# STM32F407.net
KiCad netlist of a schematic drawn in Altium Designer
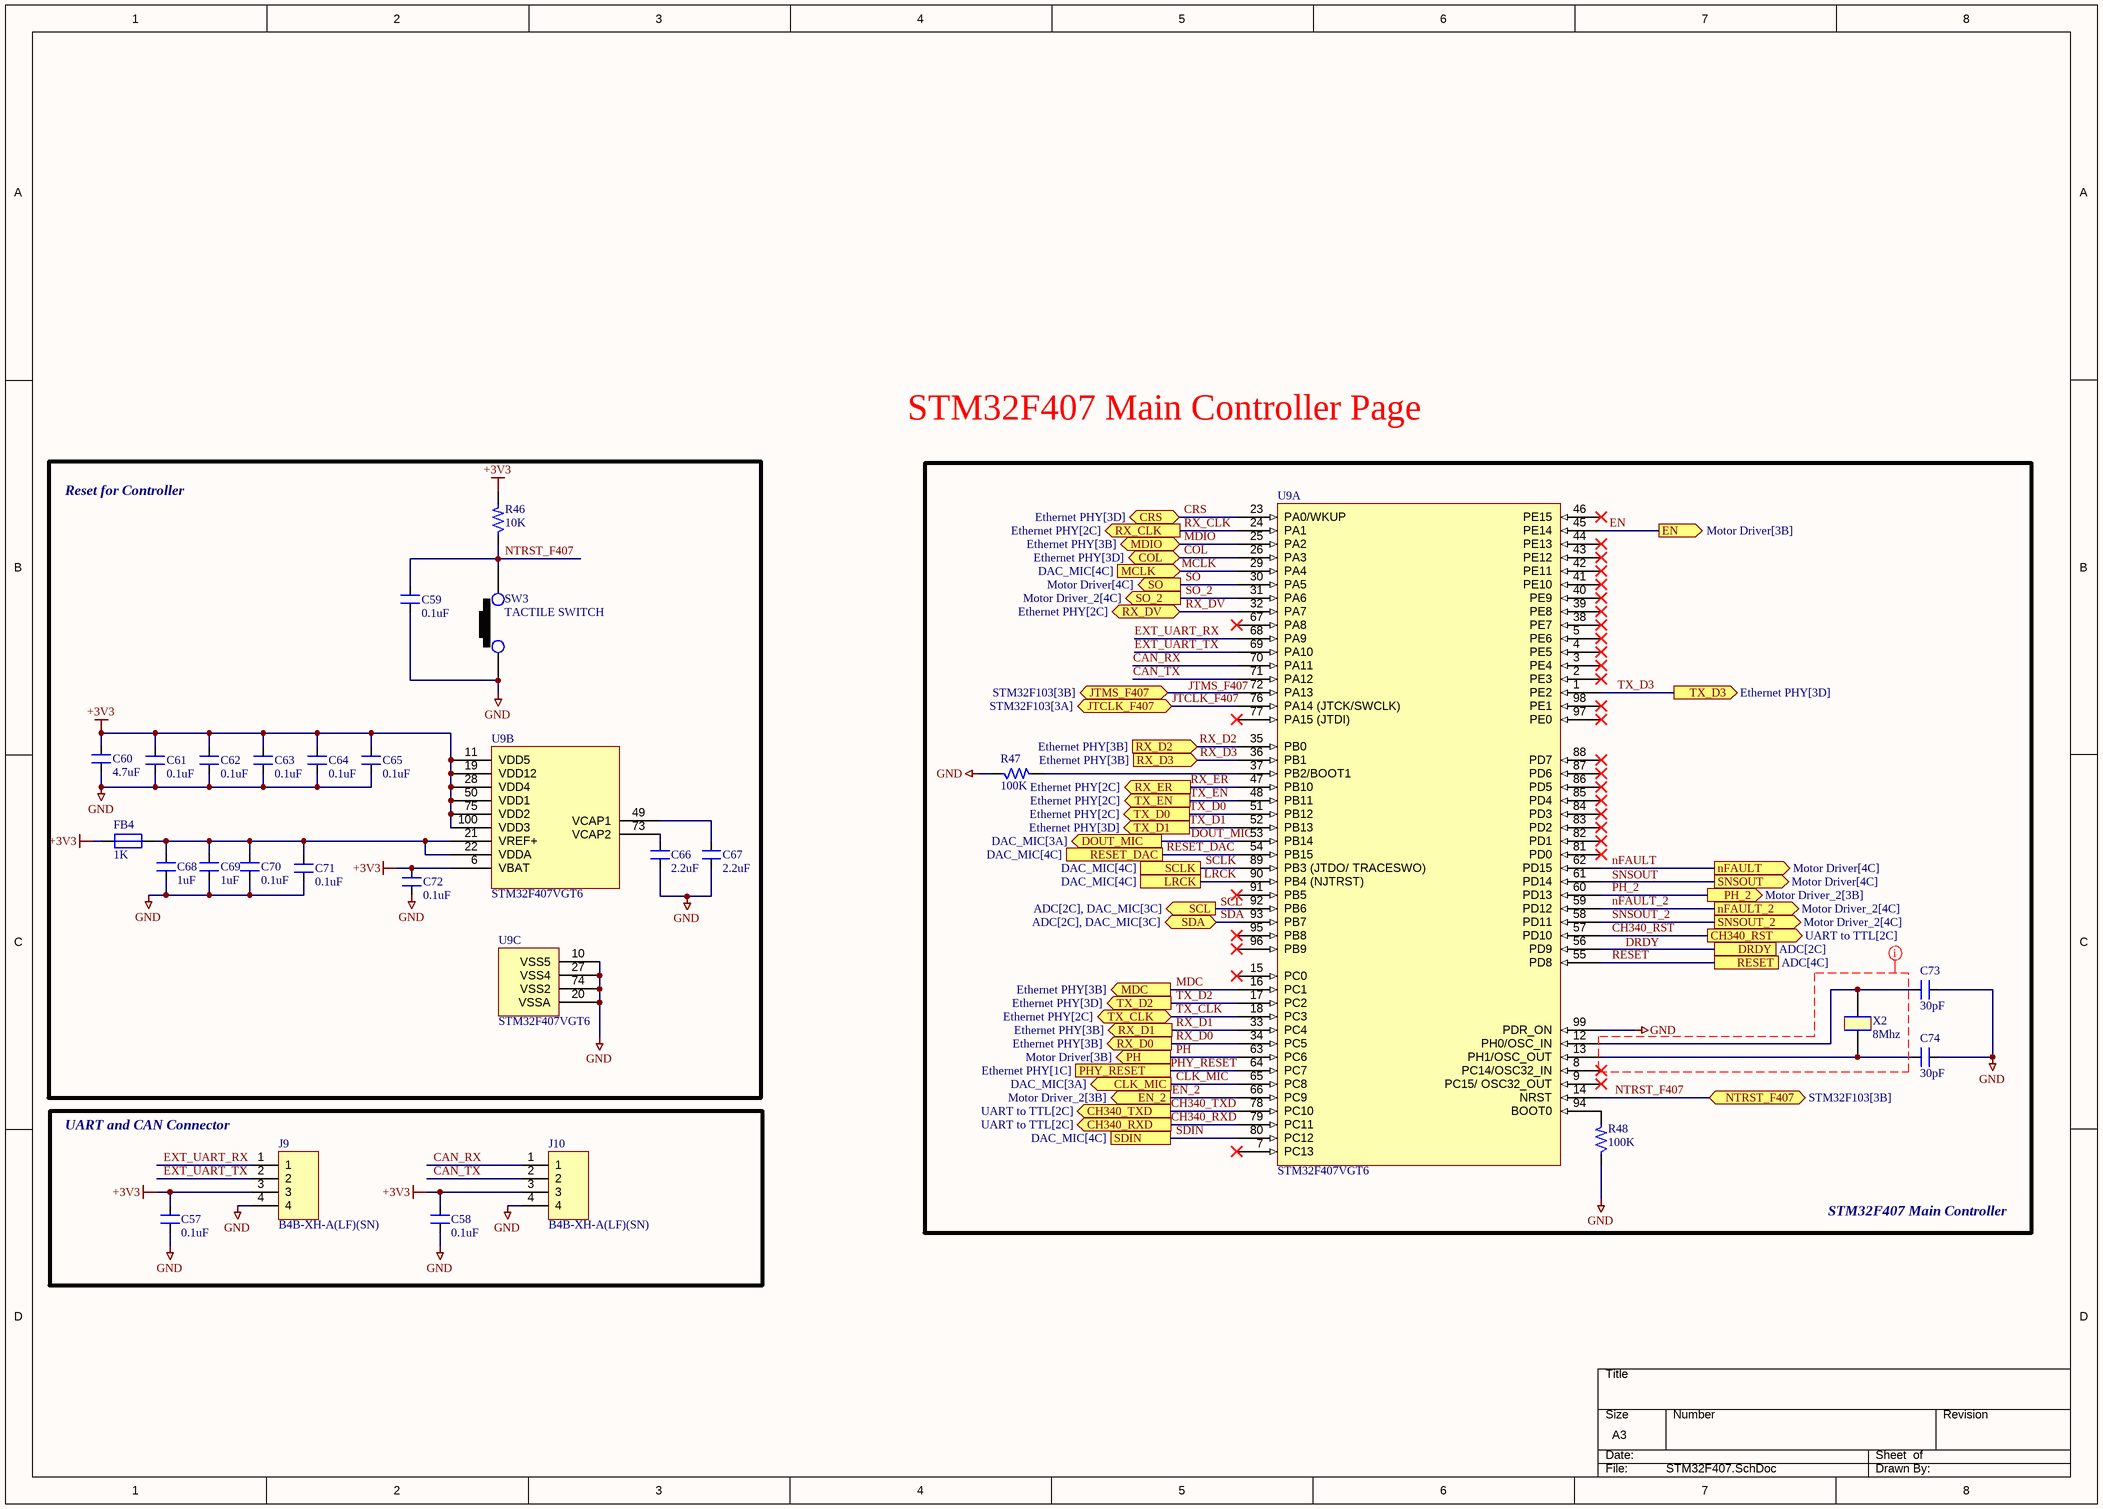
[diagram p0: STM32F407.SchDoc]

(export (version "E")
  (design (tool "Eeschema 10.0.6"))
  (components
    (comp (ref "C57")
      (value "0.1uF")
      (footprint "CAP_0805")
      (description "0.1µF ±10% 50V Ceramic Capacitor X7R 0805 (2012 Metric)")
      (fields
        (field (name "MANUFACTURER") "Samsung")
        (field (name "MANUFACTURER PART NUMBER") "CL21B104KBCNNNC")
      )
      (libsource (lib "ESTEEMPCBLIB") (part "CAP_0.1uF-50V-10%-0805"))
    )
    (comp (ref "C58")
      (value "0.1uF")
      (footprint "CAP_0805")
      (description "0.1µF ±10% 50V Ceramic Capacitor X7R 0805 (2012 Metric)")
      (fields
        (field (name "MANUFACTURER") "Samsung")
        (field (name "MANUFACTURER PART NUMBER") "CL21B104KBCNNNC")
      )
      (libsource (lib "ESTEEMPCBLIB") (part "CAP_0.1uF-50V-10%-0805"))
    )
    (comp (ref "C59")
      (value "0.1uF")
      (footprint "CAP_0805")
      (description "0.1µF ±20% 50V Ceramic Capacitor X7R 0805 (2012 Metric)")
      (fields
        (field (name "MANUFACTURER") "Samsung Electro-Mechanics")
        (field (name "MANUFACTURER PART NUMBER") "CL21B104MBCNNNC")
      )
      (libsource (lib "ESTEEMPCBLIB") (part "CAP_0.1uF-50V-20%-0805"))
    )
    (comp (ref "C60")
      (value "4.7uF")
      (footprint "CAP_0805")
      (description "4.7µF ±10% 50V Ceramic Capacitor X5R 0805 (2012 Metric)")
      (fields
        (field (name "MANUFACTURER") "Yageo")
        (field (name "MANUFACTURER PART NUMBER") "GRM21BR61H475KE51L")
      )
      (libsource (lib "ESTEEMPCBLIB") (part "CAP_4.7uF-50V-10%-0805"))
    )
    (comp (ref "C61")
      (value "0.1uF")
      (footprint "CAP_0805")
      (description "0.1µF ±20% 50V Ceramic Capacitor X7R 0805 (2012 Metric)")
      (fields
        (field (name "MANUFACTURER") "Samsung Electro-Mechanics")
        (field (name "MANUFACTURER PART NUMBER") "CL21B104MBCNNNC")
      )
      (libsource (lib "ESTEEMPCBLIB") (part "CAP_0.1uF-50V-20%-0805"))
    )
    (comp (ref "C62")
      (value "0.1uF")
      (footprint "CAP_0805")
      (description "0.1µF ±20% 50V Ceramic Capacitor X7R 0805 (2012 Metric)")
      (fields
        (field (name "MANUFACTURER") "Samsung Electro-Mechanics")
        (field (name "MANUFACTURER PART NUMBER") "CL21B104MBCNNNC")
      )
      (libsource (lib "ESTEEMPCBLIB") (part "CAP_0.1uF-50V-20%-0805"))
    )
    (comp (ref "C63")
      (value "0.1uF")
      (footprint "CAP_0805")
      (description "0.1µF ±20% 50V Ceramic Capacitor X7R 0805 (2012 Metric)")
      (fields
        (field (name "MANUFACTURER") "Samsung Electro-Mechanics")
        (field (name "MANUFACTURER PART NUMBER") "CL21B104MBCNNNC")
      )
      (libsource (lib "ESTEEMPCBLIB") (part "CAP_0.1uF-50V-20%-0805"))
    )
    (comp (ref "C64")
      (value "0.1uF")
      (footprint "CAP_0805")
      (description "0.1µF ±20% 50V Ceramic Capacitor X7R 0805 (2012 Metric)")
      (fields
        (field (name "MANUFACTURER") "Samsung Electro-Mechanics")
        (field (name "MANUFACTURER PART NUMBER") "CL21B104MBCNNNC")
      )
      (libsource (lib "ESTEEMPCBLIB") (part "CAP_0.1uF-50V-20%-0805"))
    )
    (comp (ref "C65")
      (value "0.1uF")
      (footprint "CAP_0805")
      (description "0.1µF ±20% 50V Ceramic Capacitor X7R 0805 (2012 Metric)")
      (fields
        (field (name "MANUFACTURER") "Samsung Electro-Mechanics")
        (field (name "MANUFACTURER PART NUMBER") "CL21B104MBCNNNC")
      )
      (libsource (lib "ESTEEMPCBLIB") (part "CAP_0.1uF-50V-20%-0805"))
    )
    (comp (ref "C66")
      (value "2.2uF")
      (footprint "CAP_0805")
      (description "2.2µF ±10% 25V Ceramic Capacitor X7R 0805 (2012 Metric)")
      (fields
        (field (name "MANUFACTURER") "KEMET")
        (field (name "MANUFACTURER PART NUMBER") "CL21B225KAFNFNE")
      )
      (libsource (lib "ESTEEMPCBLIB") (part "CAP_2.2uF-25V-10%-0805"))
    )
    (comp (ref "C67")
      (value "2.2uF")
      (footprint "CAP_0805")
      (description "2.2µF ±10% 25V Ceramic Capacitor X7R 0805 (2012 Metric)")
      (fields
        (field (name "MANUFACTURER") "KEMET")
        (field (name "MANUFACTURER PART NUMBER") "CL21B225KAFNFNE")
      )
      (libsource (lib "ESTEEMPCBLIB") (part "CAP_2.2uF-25V-10%-0805"))
    )
    (comp (ref "C68")
      (value "1uF")
      (footprint "CAP_0805")
      (description "1µF ±5% 50V Ceramic Capacitor X7R 0805 (2012 Metric)")
      (fields
        (field (name "MANUFACTURER") "Samsung")
        (field (name "MANUFACTURER PART NUMBER") "CC0805JKX7R9BB105")
      )
      (libsource (lib "ESTEEMPCBLIB") (part "CAP_1uF-50V-5%-0805"))
    )
    (comp (ref "C69")
      (value "1uF")
      (footprint "CAP_0805")
      (description "1µF ±5% 50V Ceramic Capacitor X7R 0805 (2012 Metric)")
      (fields
        (field (name "MANUFACTURER") "Samsung")
        (field (name "MANUFACTURER PART NUMBER") "CC0805JKX7R9BB105")
      )
      (libsource (lib "ESTEEMPCBLIB") (part "CAP_1uF-50V-5%-0805"))
    )
    (comp (ref "C70")
      (value "0.1uF")
      (footprint "CAP_0805")
      (description "0.1µF ±20% 50V Ceramic Capacitor X7R 0805 (2012 Metric)")
      (fields
        (field (name "MANUFACTURER") "Samsung Electro-Mechanics")
        (field (name "MANUFACTURER PART NUMBER") "CL21B104MBCNNNC")
      )
      (libsource (lib "ESTEEMPCBLIB") (part "CAP_0.1uF-50V-20%-0805"))
    )
    (comp (ref "C71")
      (value "0.1uF")
      (footprint "CAP_0805")
      (description "0.1µF ±20% 50V Ceramic Capacitor X7R 0805 (2012 Metric)")
      (fields
        (field (name "MANUFACTURER") "Samsung Electro-Mechanics")
        (field (name "MANUFACTURER PART NUMBER") "CL21B104MBCNNNC")
      )
      (libsource (lib "ESTEEMPCBLIB") (part "CAP_0.1uF-50V-20%-0805"))
    )
    (comp (ref "C72")
      (value "0.1uF")
      (footprint "CAP_0805")
      (description "0.1µF ±20% 50V Ceramic Capacitor X7R 0805 (2012 Metric)")
      (fields
        (field (name "MANUFACTURER") "Samsung Electro-Mechanics")
        (field (name "MANUFACTURER PART NUMBER") "CL21B104MBCNNNC")
      )
      (libsource (lib "ESTEEMPCBLIB") (part "CAP_0.1uF-50V-20%-0805"))
    )
    (comp (ref "C73")
      (value "30pF")
      (footprint "CAP_0805")
      (description "±10% 50V Ceramic Capacitor C0G, NP0 0805 (2012 Metric)")
      (fields
        (field (name "MANUFACTURER PART NUMBER") "C0805C300K5GAC7800")
        (field (name "MANUFACTURER") "KEMET")
      )
      (libsource (lib "ESTEEMPCBLIB") (part "CAP_30pF-50V-10%-0805"))
    )
    (comp (ref "C74")
      (value "30pF")
      (footprint "CAP_0805")
      (description "±10% 50V Ceramic Capacitor C0G, NP0 0805 (2012 Metric)")
      (fields
        (field (name "MANUFACTURER PART NUMBER") "C0805C300K5GAC7800")
        (field (name "MANUFACTURER") "KEMET")
      )
      (libsource (lib "ESTEEMPCBLIB") (part "CAP_30pF-50V-10%-0805"))
    )
    (comp (ref "FB4")
      (value "1K")
      (footprint "IND_0805")
      (description "1 kOhms @ 100MHz 1 Power Line Ferrite Bead 0805 (2012 Metric) 1.6A")
      (fields
        (field (name "MANUFACTURER") "Laird")
        (field (name "MANUFACTURER PART NUMBER") "BLM21SP102SH1D")
      )
      (libsource (lib "ESTEEMPCBLIB") (part "FB_1K-100MHZ-1.6A-0805"))
    )
    (comp (ref "J9")
      (value "B4B-XH-A(LF)(SN)")
      (footprint "CON4_100_B4B-XH-A_TH_ST")
      (description "4 Pins, 1 Row 2.54mm Pitch, straight Connector, male")
      (fields (field (name "MANUFACTURER") "Wurth Electronics") (field (name "MATING PART NUMBER") "XHP-4"))
      (libsource (lib "ESTEEMPCBLIB") (part "CON-PLG_4X1-100-ST-TH"))
    )
    (comp (ref "J10")
      (value "B4B-XH-A(LF)(SN)")
      (footprint "CON4_100_B4B-XH-A_TH_ST")
      (description "4 Pins, 1 Row 2.54mm Pitch, straight Connector, male")
      (fields (field (name "MANUFACTURER") "Wurth Electronics") (field (name "MATING PART NUMBER") "XHP-4"))
      (libsource (lib "ESTEEMPCBLIB") (part "CON-PLG_4X1-100-ST-TH"))
    )
    (comp (ref "R46")
      (value "10K")
      (footprint "RES_0603")
      (description "10 kOhms ±1% 0.1W, 1/10W Chip Resistor 0603 (1608 Metric) Automotive AEC-Q200 Thick Film")
      (fields (field (name "MANUFACTURER") "Walsin") (field (name "MANUFACTURER PART NUMBER") "WR06X1002FTL"))
      (libsource (lib "ESTEEMPCBLIB") (part "RES_10K-0.1W-1%-0603"))
    )
    (comp (ref "R47")
      (value "100K")
      (footprint "RES_0603")
      (description "100 kOhms ±1% 0.1W, 1/10W Chip Resistor 0603 (1608 Metric) Automotive AEC-Q200 Thick Film")
      (fields
        (field (name "MANUFACTURER") "Stackpole Electronics")
        (field (name "MANUFACTURER PART NUMBER") "RMCF0603FT100K")
      )
      (libsource (lib "ESTEEMPCBLIB") (part "RES_100K-0.1W-1%-0603"))
    )
    (comp (ref "R48")
      (value "100K")
      (footprint "RES_0603")
      (description "100 kOhms ±1% 0.1W, 1/10W Chip Resistor 0603 (1608 Metric) Automotive AEC-Q200 Thick Film")
      (fields
        (field (name "MANUFACTURER") "Stackpole Electronics")
        (field (name "MANUFACTURER PART NUMBER") "RMCF0603FT100K")
      )
      (libsource (lib "ESTEEMPCBLIB") (part "RES_100K-0.1W-1%-0603"))
    )
    (comp (ref "SW3")
      (value "TACTILE SWITCH")
      (footprint "SW_342_SMD")
      (description "Tactile Switch SPST-NO Top Actuated Surface Mount")
      (fields
        (field (name "MANUFACTURER") "ITT C&K")
        (field (name "MANUFACTURER PART NUMBER") "RS-282G05A3-SMRT")
      )
      (libsource (lib "ESTEEMPCBLIB") (part "SW1_RS-282G05A3-SMRT-SMD"))
    )
    (comp (ref "U9")
      (value "STM32F407VGT6")
      (footprint "QFN100_19.6_669_58X10_SMD")
      (description "ARM® Cortex®-M4 STM32F4 Microcontroller IC 32-Bit 168MHz 1MB (1M x 8) FLASH 100-LQFP (14x14)")
      (fields (field (name "MANUFACTURER") "STMicroelectronics"))
      (libsource (lib "ESTEEMPCBLIB") (part "IC_STM32F407VGT6"))
    )
    (comp (ref "X2")
      (value "8Mhz")
      (footprint "XTAL_314_240X47_SMD")
      (description "8MHz ±30ppm Crystal 32pF 60 Ohms HC-49/US")
      (fields
        (field (name "MANUFACTURER") "Fox Electronics")
        (field (name "MANUFACTURER PART NUMBER") "ECS-80-32-5PX-TR")
      )
      (libsource (lib "ESTEEMPCBLIB") (part "XTAL_8MHZ-ECS-80-32-5PX-SMD"))
    )
  )
  (nets
    (net (code "1") (name "+3V3") (class "Default")
      (node (ref "C57") (pin "2") (pinfunction "2_2") (pintype "passive"))
      (node (ref "C58") (pin "2") (pinfunction "2_2") (pintype "passive"))
      (node (ref "C60") (pin "2") (pinfunction "2_2") (pintype "passive"))
      (node (ref "C61") (pin "2") (pinfunction "2_2") (pintype "passive"))
      (node (ref "C62") (pin "2") (pinfunction "2_2") (pintype "passive"))
      (node (ref "C63") (pin "2") (pinfunction "2_2") (pintype "passive"))
      (node (ref "C64") (pin "2") (pinfunction "2_2") (pintype "passive"))
      (node (ref "C65") (pin "2") (pinfunction "2_2") (pintype "passive"))
      (node (ref "C72") (pin "2") (pinfunction "2_2") (pintype "passive"))
      (node (ref "FB4") (pin "1") (pinfunction "1_1") (pintype "passive"))
      (node (ref "J10") (pin "3") (pinfunction "3_3") (pintype "passive"))
      (node (ref "J9") (pin "3") (pinfunction "3_3") (pintype "passive"))
      (node (ref "R46") (pin "2") (pinfunction "2_2") (pintype "passive"))
      (node (ref "U9") (pin "100") (pinfunction "VDD3_100") (pintype "passive"))
      (node (ref "U9") (pin "11") (pinfunction "VDD5_11") (pintype "passive"))
      (node (ref "U9") (pin "19") (pinfunction "VDD12_19") (pintype "passive"))
      (node (ref "U9") (pin "28") (pinfunction "VDD4_28") (pintype "passive"))
      (node (ref "U9") (pin "50") (pinfunction "VDD1_50") (pintype "passive"))
      (node (ref "U9") (pin "6") (pinfunction "VBAT_6") (pintype "passive"))
      (node (ref "U9") (pin "75") (pinfunction "VDD2_75") (pintype "passive"))
    )
    (net (code "2") (name "/CAN_RX") (class "Default")
      (node (ref "J10") (pin "1") (pinfunction "1_1") (pintype "passive"))
      (node (ref "U9") (pin "70") (pinfunction "PA11_70") (pintype "input"))
    )
    (net (code "3") (name "/CAN_TX") (class "Default")
      (node (ref "J10") (pin "2") (pinfunction "2_2") (pintype "passive"))
      (node (ref "U9") (pin "71") (pinfunction "PA12_71") (pintype "input"))
    )
    (net (code "4") (name "/CH340_RST") (class "Default")
      (node (ref "U9") (pin "57") (pinfunction "PD10_57") (pintype "input"))
    )
    (net (code "5") (name "/CH340_RXD") (class "Default")
      (node (ref "U9") (pin "79") (pinfunction "PC11_79") (pintype "input"))
    )
    (net (code "6") (name "/CH340_TXD") (class "Default")
      (node (ref "U9") (pin "78") (pinfunction "PC10_78") (pintype "input"))
    )
    (net (code "7") (name "/CLK_MIC") (class "Default")
      (node (ref "U9") (pin "65") (pinfunction "PC8_65") (pintype "input"))
    )
    (net (code "8") (name "/COL") (class "Default")
      (node (ref "U9") (pin "26") (pinfunction "PA3_26") (pintype "input"))
    )
    (net (code "9") (name "/CRS") (class "Default")
      (node (ref "U9") (pin "23") (pinfunction "PA0/WKUP_23") (pintype "input"))
    )
    (net (code "10") (name "/DOUT_MIC") (class "Default")
      (node (ref "U9") (pin "53") (pinfunction "PB14_53") (pintype "input"))
    )
    (net (code "11") (name "/DRDY") (class "Default")
      (node (ref "U9") (pin "56") (pinfunction "PD9_56") (pintype "input"))
    )
    (net (code "12") (name "/EN") (class "Default")
      (node (ref "U9") (pin "45") (pinfunction "PE14_45") (pintype "input"))
    )
    (net (code "13") (name "/EN_2") (class "Default")
      (node (ref "U9") (pin "66") (pinfunction "PC9_66") (pintype "input"))
    )
    (net (code "14") (name "/EXT_UART_RX") (class "Default")
      (node (ref "J9") (pin "1") (pinfunction "1_1") (pintype "passive"))
      (node (ref "U9") (pin "68") (pinfunction "PA9_68") (pintype "input"))
    )
    (net (code "15") (name "/EXT_UART_TX") (class "Default")
      (node (ref "J9") (pin "2") (pinfunction "2_2") (pintype "passive"))
      (node (ref "U9") (pin "69") (pinfunction "PA10_69") (pintype "input"))
    )
    (net (code "16") (name "/JTCLK_F407") (class "Default")
      (node (ref "U9") (pin "76") (pinfunction "PA14_(JTCK/SWCLK)_76") (pintype "input"))
    )
    (net (code "17") (name "/JTMS_F407") (class "Default")
      (node (ref "U9") (pin "72") (pinfunction "PA13_72") (pintype "input"))
    )
    (net (code "18") (name "/LRCK") (class "Default")
      (node (ref "U9") (pin "90") (pinfunction "PB4_(NJTRST)_90") (pintype "input"))
    )
    (net (code "19") (name "/MCLK") (class "Default")
      (node (ref "U9") (pin "29") (pinfunction "PA4_29") (pintype "input"))
    )
    (net (code "20") (name "/MDC") (class "Default")
      (node (ref "U9") (pin "16") (pinfunction "PC1_16") (pintype "input"))
    )
    (net (code "21") (name "/MDIO") (class "Default")
      (node (ref "U9") (pin "25") (pinfunction "PA2_25") (pintype "input"))
    )
    (net (code "22") (name "/NTRST_F407") (class "Default")
      (node (ref "C59") (pin "2") (pinfunction "2_2") (pintype "passive"))
      (node (ref "R46") (pin "1") (pinfunction "1_1") (pintype "passive"))
      (node (ref "SW3") (pin "2") (pinfunction "2_2") (pintype "passive"))
      (node (ref "U9") (pin "14") (pinfunction "NRST_14") (pintype "input"))
    )
    (net (code "23") (name "/PH") (class "Default")
      (node (ref "U9") (pin "63") (pinfunction "PC6_63") (pintype "input"))
    )
    (net (code "24") (name "/PHY_RESET") (class "Default")
      (node (ref "U9") (pin "64") (pinfunction "PC7_64") (pintype "input"))
    )
    (net (code "25") (name "/PH_2") (class "Default")
      (node (ref "U9") (pin "60") (pinfunction "PD13_60") (pintype "input"))
    )
    (net (code "26") (name "/RESET") (class "Default")
      (node (ref "U9") (pin "55") (pinfunction "PD8_55") (pintype "input"))
    )
    (net (code "27") (name "/RESET_DAC") (class "Default")
      (node (ref "U9") (pin "54") (pinfunction "PB15_54") (pintype "input"))
    )
    (net (code "28") (name "/RX_CLK") (class "Default")
      (node (ref "U9") (pin "24") (pinfunction "PA1_24") (pintype "input"))
    )
    (net (code "29") (name "/RX_D0") (class "Default")
      (node (ref "U9") (pin "34") (pinfunction "PC5_34") (pintype "input"))
    )
    (net (code "30") (name "/RX_D1") (class "Default")
      (node (ref "U9") (pin "33") (pinfunction "PC4_33") (pintype "input"))
    )
    (net (code "31") (name "/RX_D2") (class "Default")
      (node (ref "U9") (pin "35") (pinfunction "PB0_35") (pintype "input"))
    )
    (net (code "32") (name "/RX_D3") (class "Default")
      (node (ref "U9") (pin "36") (pinfunction "PB1_36") (pintype "input"))
    )
    (net (code "33") (name "/RX_DV") (class "Default")
      (node (ref "U9") (pin "32") (pinfunction "PA7_32") (pintype "input"))
    )
    (net (code "34") (name "/RX_ER") (class "Default")
      (node (ref "U9") (pin "47") (pinfunction "PB10_47") (pintype "input"))
    )
    (net (code "35") (name "/SCL") (class "Default")
      (node (ref "U9") (pin "92") (pinfunction "PB6_92") (pintype "input"))
    )
    (net (code "36") (name "/SCLK") (class "Default")
      (node (ref "U9") (pin "89") (pinfunction "PB3_(JTDO/_TRACESWO)_89") (pintype "input"))
    )
    (net (code "37") (name "/SDA") (class "Default")
      (node (ref "U9") (pin "93") (pinfunction "PB7_93") (pintype "input"))
    )
    (net (code "38") (name "/SDIN") (class "Default")
      (node (ref "U9") (pin "80") (pinfunction "PC12_80") (pintype "input"))
    )
    (net (code "39") (name "/SNSOUT") (class "Default")
      (node (ref "U9") (pin "61") (pinfunction "PD14_61") (pintype "input"))
    )
    (net (code "40") (name "/SNSOUT_2") (class "Default")
      (node (ref "U9") (pin "58") (pinfunction "PD11_58") (pintype "input"))
    )
    (net (code "41") (name "/SO") (class "Default")
      (node (ref "U9") (pin "30") (pinfunction "PA5_30") (pintype "input"))
    )
    (net (code "42") (name "/SO_2") (class "Default")
      (node (ref "U9") (pin "31") (pinfunction "PA6_31") (pintype "input"))
    )
    (net (code "43") (name "/TX_CLK") (class "Default")
      (node (ref "U9") (pin "18") (pinfunction "PC3_18") (pintype "input"))
    )
    (net (code "44") (name "/TX_D0") (class "Default")
      (node (ref "U9") (pin "51") (pinfunction "PB12_51") (pintype "input"))
    )
    (net (code "45") (name "/TX_D1") (class "Default")
      (node (ref "U9") (pin "52") (pinfunction "PB13_52") (pintype "input"))
    )
    (net (code "46") (name "/TX_D2") (class "Default")
      (node (ref "U9") (pin "17") (pinfunction "PC2_17") (pintype "input"))
    )
    (net (code "47") (name "/TX_D3") (class "Default")
      (node (ref "U9") (pin "1") (pinfunction "PE2_1") (pintype "input"))
    )
    (net (code "48") (name "/TX_EN") (class "Default")
      (node (ref "U9") (pin "48") (pinfunction "PB11_48") (pintype "input"))
    )
    (net (code "49") (name "/nFAULT") (class "Default")
      (node (ref "U9") (pin "62") (pinfunction "PD15_62") (pintype "input"))
    )
    (net (code "50") (name "/nFAULT_2") (class "Default")
      (node (ref "U9") (pin "59") (pinfunction "PD12_59") (pintype "input"))
    )
    (net (code "51") (name "GND") (class "Default")
      (node (ref "C57") (pin "1") (pinfunction "1_1") (pintype "passive"))
      (node (ref "C58") (pin "1") (pinfunction "1_1") (pintype "passive"))
      (node (ref "C59") (pin "1") (pinfunction "1_1") (pintype "passive"))
      (node (ref "C60") (pin "1") (pinfunction "1_1") (pintype "passive"))
      (node (ref "C61") (pin "1") (pinfunction "1_1") (pintype "passive"))
      (node (ref "C62") (pin "1") (pinfunction "1_1") (pintype "passive"))
      (node (ref "C63") (pin "1") (pinfunction "1_1") (pintype "passive"))
      (node (ref "C64") (pin "1") (pinfunction "1_1") (pintype "passive"))
      (node (ref "C65") (pin "1") (pinfunction "1_1") (pintype "passive"))
      (node (ref "C66") (pin "1") (pinfunction "1_1") (pintype "passive"))
      (node (ref "C67") (pin "1") (pinfunction "1_1") (pintype "passive"))
      (node (ref "C68") (pin "1") (pinfunction "1_1") (pintype "passive"))
      (node (ref "C69") (pin "1") (pinfunction "1_1") (pintype "passive"))
      (node (ref "C70") (pin "1") (pinfunction "1_1") (pintype "passive"))
      (node (ref "C71") (pin "1") (pinfunction "1_1") (pintype "passive"))
      (node (ref "C72") (pin "1") (pinfunction "1_1") (pintype "passive"))
      (node (ref "C73") (pin "2") (pinfunction "2_2") (pintype "passive"))
      (node (ref "C74") (pin "2") (pinfunction "2_2") (pintype "passive"))
      (node (ref "J10") (pin "4") (pinfunction "4_4") (pintype "passive"))
      (node (ref "J9") (pin "4") (pinfunction "4_4") (pintype "passive"))
      (node (ref "R47") (pin "1") (pinfunction "1_1") (pintype "passive"))
      (node (ref "R48") (pin "1") (pinfunction "1_1") (pintype "passive"))
      (node (ref "SW3") (pin "1") (pinfunction "1_1") (pintype "passive"))
      (node (ref "U9") (pin "10") (pinfunction "VSS5_10") (pintype "passive"))
      (node (ref "U9") (pin "20") (pinfunction "VSSA_20") (pintype "passive"))
      (node (ref "U9") (pin "27") (pinfunction "VSS4_27") (pintype "passive"))
      (node (ref "U9") (pin "74") (pinfunction "VSS2_74") (pintype "passive"))
      (node (ref "U9") (pin "99") (pinfunction "PDR_ON_99") (pintype "input"))
    )
    (net (code "52") (name "Net-(U9A-BOOT0)") (class "Default")
      (node (ref "R48") (pin "2") (pinfunction "2_2") (pintype "passive"))
      (node (ref "U9") (pin "94") (pinfunction "BOOT0_94") (pintype "input"))
    )
    (net (code "53") (name "Net-(U9A-PB2{slash}BOOT1)") (class "Default")
      (node (ref "R47") (pin "2") (pinfunction "2_2") (pintype "passive"))
      (node (ref "U9") (pin "37") (pinfunction "PB2/BOOT1_37") (pintype "input"))
    )
    (net (code "54") (name "Net-(U9A-PH0{slash}OSC_IN)") (class "Default")
      (node (ref "C73") (pin "1") (pinfunction "1_1") (pintype "passive"))
      (node (ref "U9") (pin "12") (pinfunction "PH0/OSC_IN_12") (pintype "input"))
      (node (ref "X2") (pin "2") (pinfunction "2_2") (pintype "passive"))
    )
    (net (code "55") (name "Net-(U9A-PH1{slash}OSC_OUT)") (class "Default")
      (node (ref "C74") (pin "1") (pinfunction "1_1") (pintype "passive"))
      (node (ref "U9") (pin "13") (pinfunction "PH1/OSC_OUT_13") (pintype "input"))
      (node (ref "X2") (pin "1") (pinfunction "1_1") (pintype "passive"))
    )
    (net (code "56") (name "Net-(U9B-VCAP1)") (class "Default")
      (node (ref "C67") (pin "2") (pinfunction "2_2") (pintype "passive"))
      (node (ref "U9") (pin "49") (pinfunction "VCAP1_49") (pintype "passive"))
    )
    (net (code "57") (name "Net-(U9B-VCAP2)") (class "Default")
      (node (ref "C66") (pin "2") (pinfunction "2_2") (pintype "passive"))
      (node (ref "U9") (pin "73") (pinfunction "VCAP2_73") (pintype "passive"))
    )
    (net (code "58") (name "Net-(U9B-VDDA)") (class "Default")
      (node (ref "C68") (pin "2") (pinfunction "2_2") (pintype "passive"))
      (node (ref "C69") (pin "2") (pinfunction "2_2") (pintype "passive"))
      (node (ref "C70") (pin "2") (pinfunction "2_2") (pintype "passive"))
      (node (ref "C71") (pin "2") (pinfunction "2_2") (pintype "passive"))
      (node (ref "FB4") (pin "2") (pinfunction "2_2") (pintype "passive"))
      (node (ref "U9") (pin "21") (pinfunction "VREF+_21") (pintype "passive"))
      (node (ref "U9") (pin "22") (pinfunction "VDDA_22") (pintype "passive"))
    )
    (net (code "59") (name "unconnected-(U9A-PA8-Pad67)") (class "Default")
      (node (ref "U9") (pin "67") (pinfunction "PA8_67") (pintype "input+no_connect"))
    )
    (net (code "60") (name "unconnected-(U9A-PA15_(JTDI)-Pad77)") (class "Default")
      (node (ref "U9") (pin "77") (pinfunction "PA15_(JTDI)_77") (pintype "input+no_connect"))
    )
    (net (code "61") (name "unconnected-(U9A-PB5-Pad91)") (class "Default")
      (node (ref "U9") (pin "91") (pinfunction "PB5_91") (pintype "input+no_connect"))
    )
    (net (code "62") (name "unconnected-(U9A-PB8-Pad95)") (class "Default")
      (node (ref "U9") (pin "95") (pinfunction "PB8_95") (pintype "input+no_connect"))
    )
    (net (code "63") (name "unconnected-(U9A-PB9-Pad96)") (class "Default")
      (node (ref "U9") (pin "96") (pinfunction "PB9_96") (pintype "input+no_connect"))
    )
    (net (code "64") (name "unconnected-(U9A-PC0-Pad15)") (class "Default")
      (node (ref "U9") (pin "15") (pinfunction "PC0_15") (pintype "input+no_connect"))
    )
    (net (code "65") (name "unconnected-(U9A-PC13-Pad7)") (class "Default")
      (node (ref "U9") (pin "7") (pinfunction "PC13_7") (pintype "input+no_connect"))
    )
    (net (code "66") (name "unconnected-(U9A-PC14{slash}OSC32_IN-Pad8)") (class "Default")
      (node (ref "U9") (pin "8") (pinfunction "PC14/OSC32_IN_8") (pintype "input+no_connect"))
    )
    (net (code "67") (name "unconnected-(U9A-PC15{slash}_OSC32_OUT-Pad9)") (class "Default")
      (node (ref "U9") (pin "9") (pinfunction "PC15/_OSC32_OUT_9") (pintype "input+no_connect"))
    )
    (net (code "68") (name "unconnected-(U9A-PD0-Pad81)") (class "Default")
      (node (ref "U9") (pin "81") (pinfunction "PD0_81") (pintype "input+no_connect"))
    )
    (net (code "69") (name "unconnected-(U9A-PD1-Pad82)") (class "Default")
      (node (ref "U9") (pin "82") (pinfunction "PD1_82") (pintype "input+no_connect"))
    )
    (net (code "70") (name "unconnected-(U9A-PD2-Pad83)") (class "Default")
      (node (ref "U9") (pin "83") (pinfunction "PD2_83") (pintype "input+no_connect"))
    )
    (net (code "71") (name "unconnected-(U9A-PD3-Pad84)") (class "Default")
      (node (ref "U9") (pin "84") (pinfunction "PD3_84") (pintype "input+no_connect"))
    )
    (net (code "72") (name "unconnected-(U9A-PD4-Pad85)") (class "Default")
      (node (ref "U9") (pin "85") (pinfunction "PD4_85") (pintype "input+no_connect"))
    )
    (net (code "73") (name "unconnected-(U9A-PD5-Pad86)") (class "Default")
      (node (ref "U9") (pin "86") (pinfunction "PD5_86") (pintype "input+no_connect"))
    )
    (net (code "74") (name "unconnected-(U9A-PD6-Pad87)") (class "Default")
      (node (ref "U9") (pin "87") (pinfunction "PD6_87") (pintype "input+no_connect"))
    )
    (net (code "75") (name "unconnected-(U9A-PD7-Pad88)") (class "Default")
      (node (ref "U9") (pin "88") (pinfunction "PD7_88") (pintype "input+no_connect"))
    )
    (net (code "76") (name "unconnected-(U9A-PE0-Pad97)") (class "Default")
      (node (ref "U9") (pin "97") (pinfunction "PE0_97") (pintype "input+no_connect"))
    )
    (net (code "77") (name "unconnected-(U9A-PE1-Pad98)") (class "Default")
      (node (ref "U9") (pin "98") (pinfunction "PE1_98") (pintype "input+no_connect"))
    )
    (net (code "78") (name "unconnected-(U9A-PE3-Pad2)") (class "Default")
      (node (ref "U9") (pin "2") (pinfunction "PE3_2") (pintype "input+no_connect"))
    )
    (net (code "79") (name "unconnected-(U9A-PE4-Pad3)") (class "Default")
      (node (ref "U9") (pin "3") (pinfunction "PE4_3") (pintype "input+no_connect"))
    )
    (net (code "80") (name "unconnected-(U9A-PE5-Pad4)") (class "Default")
      (node (ref "U9") (pin "4") (pinfunction "PE5_4") (pintype "input+no_connect"))
    )
    (net (code "81") (name "unconnected-(U9A-PE6-Pad5)") (class "Default")
      (node (ref "U9") (pin "5") (pinfunction "PE6_5") (pintype "input+no_connect"))
    )
    (net (code "82") (name "unconnected-(U9A-PE7-Pad38)") (class "Default")
      (node (ref "U9") (pin "38") (pinfunction "PE7_38") (pintype "input+no_connect"))
    )
    (net (code "83") (name "unconnected-(U9A-PE8-Pad39)") (class "Default")
      (node (ref "U9") (pin "39") (pinfunction "PE8_39") (pintype "input+no_connect"))
    )
    (net (code "84") (name "unconnected-(U9A-PE9-Pad40)") (class "Default")
      (node (ref "U9") (pin "40") (pinfunction "PE9_40") (pintype "input+no_connect"))
    )
    (net (code "85") (name "unconnected-(U9A-PE10-Pad41)") (class "Default")
      (node (ref "U9") (pin "41") (pinfunction "PE10_41") (pintype "input+no_connect"))
    )
    (net (code "86") (name "unconnected-(U9A-PE11-Pad42)") (class "Default")
      (node (ref "U9") (pin "42") (pinfunction "PE11_42") (pintype "input+no_connect"))
    )
    (net (code "87") (name "unconnected-(U9A-PE12-Pad43)") (class "Default")
      (node (ref "U9") (pin "43") (pinfunction "PE12_43") (pintype "input+no_connect"))
    )
    (net (code "88") (name "unconnected-(U9A-PE13-Pad44)") (class "Default")
      (node (ref "U9") (pin "44") (pinfunction "PE13_44") (pintype "input+no_connect"))
    )
    (net (code "89") (name "unconnected-(U9A-PE15-Pad46)") (class "Default")
      (node (ref "U9") (pin "46") (pinfunction "PE15_46") (pintype "input+no_connect"))
    )
  )
)
